# Christmas_Star.net
KiCad netlist of a schematic drawn in EAGLE
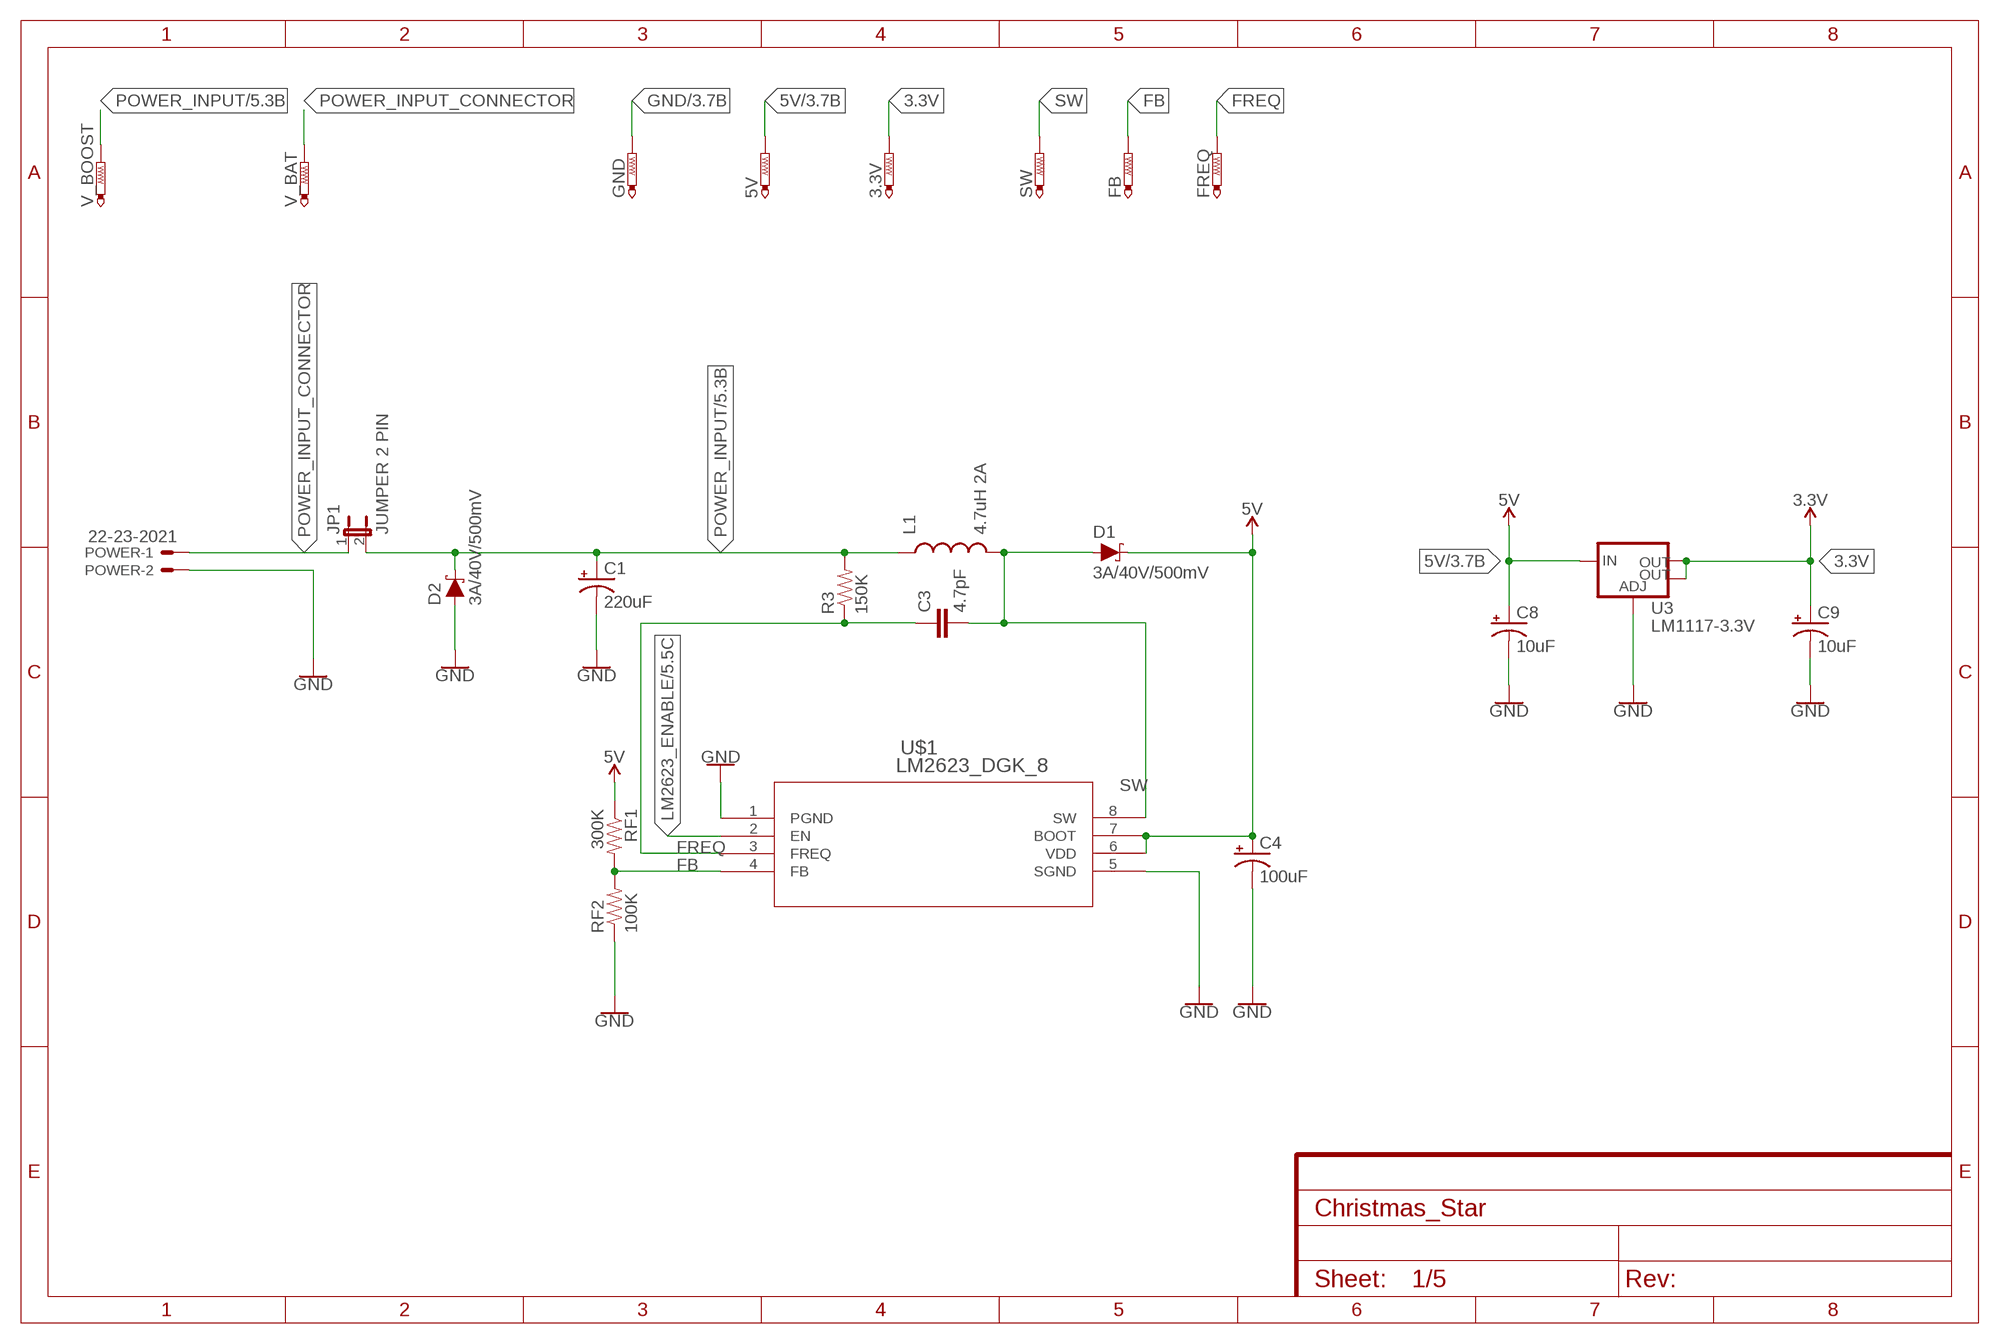
[diagram p0: schematic, sheet 1]
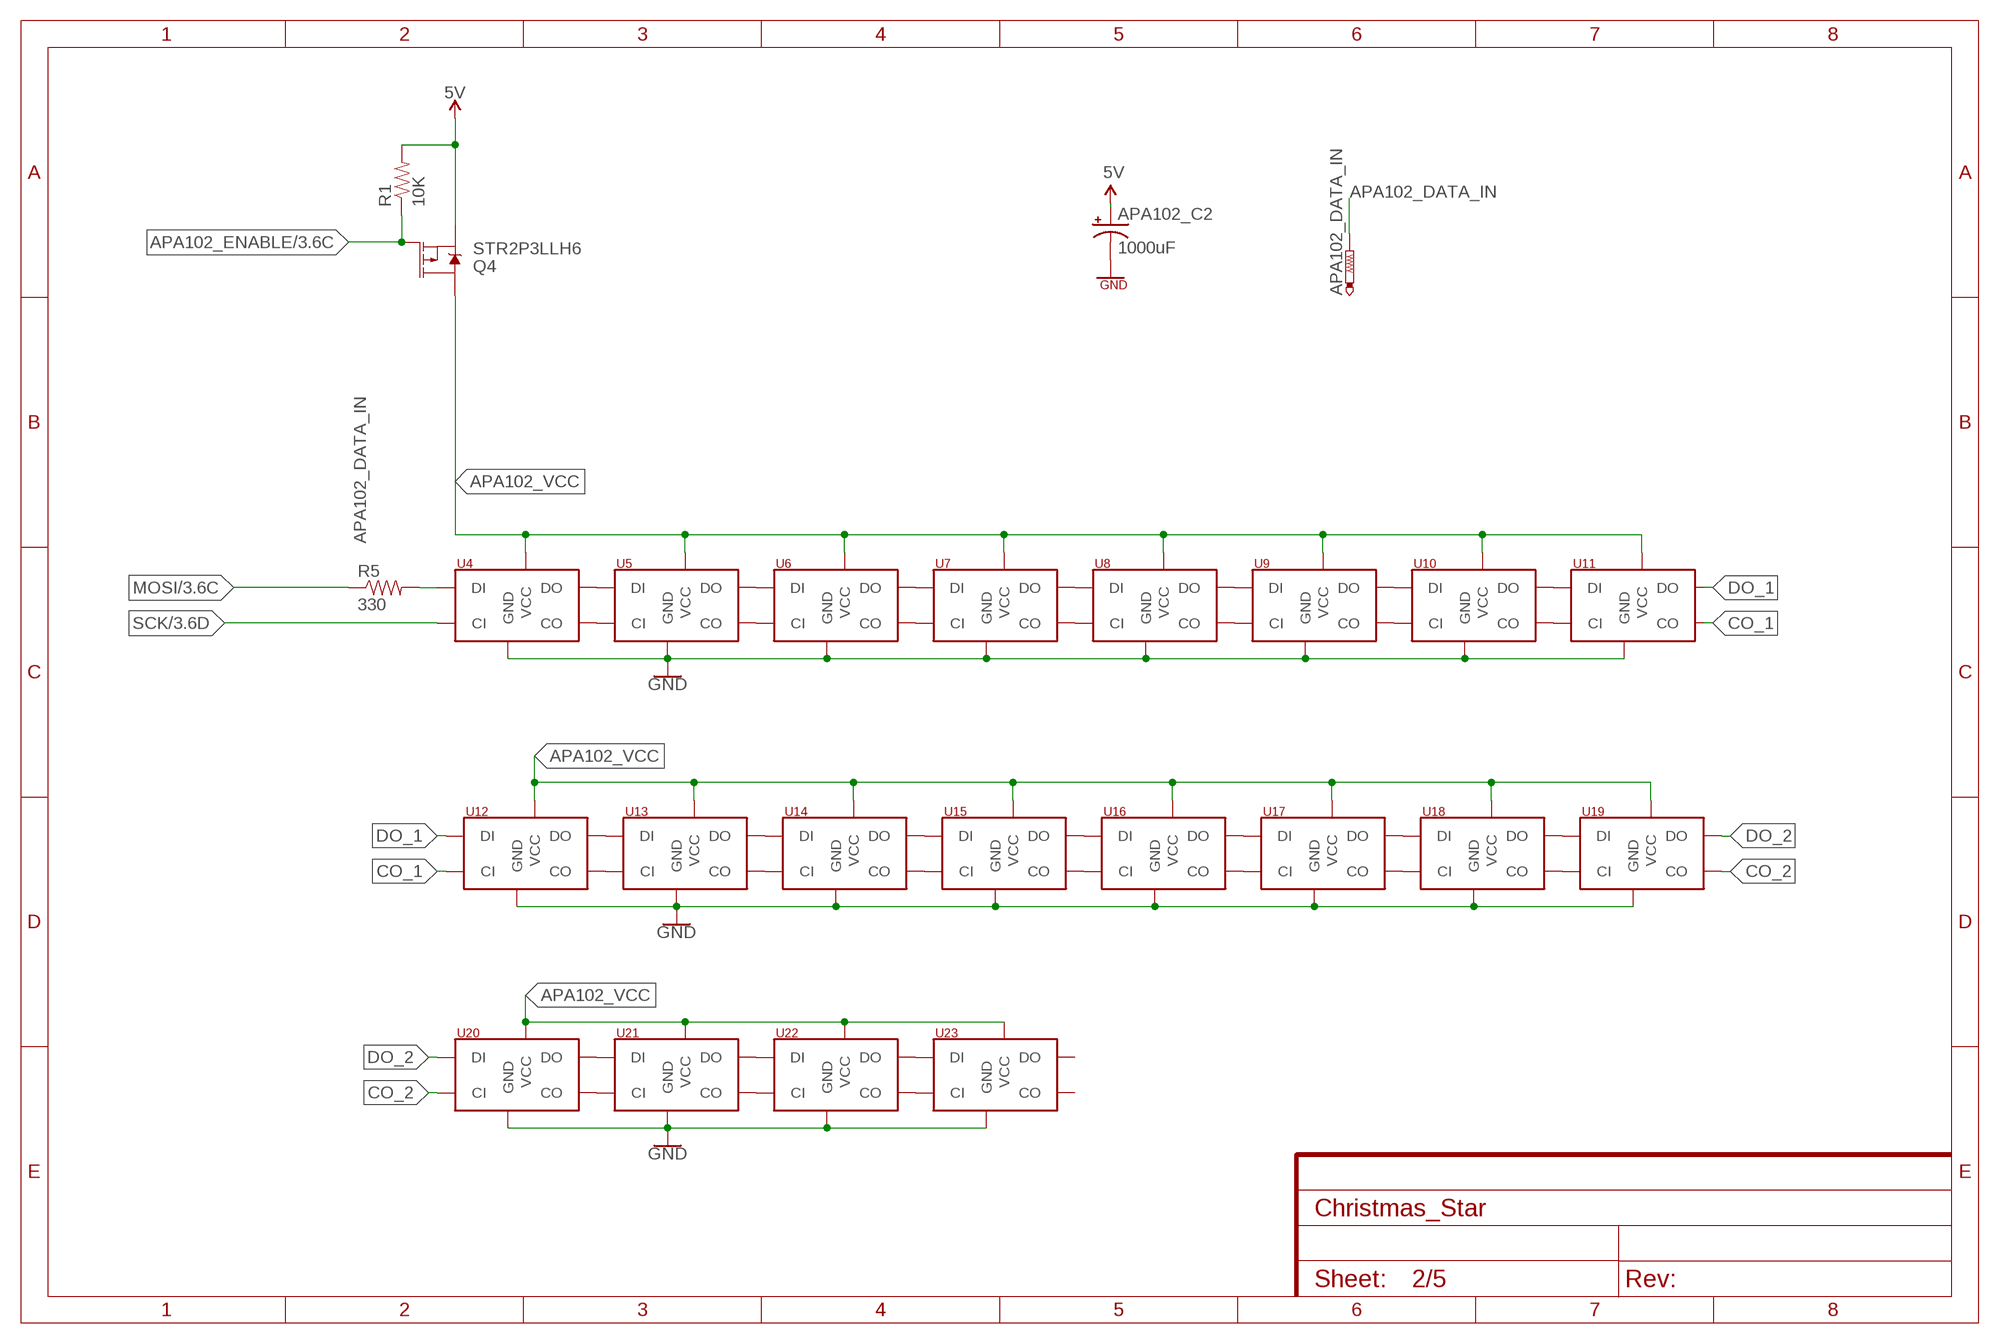
[diagram p1: schematic, sheet 2]
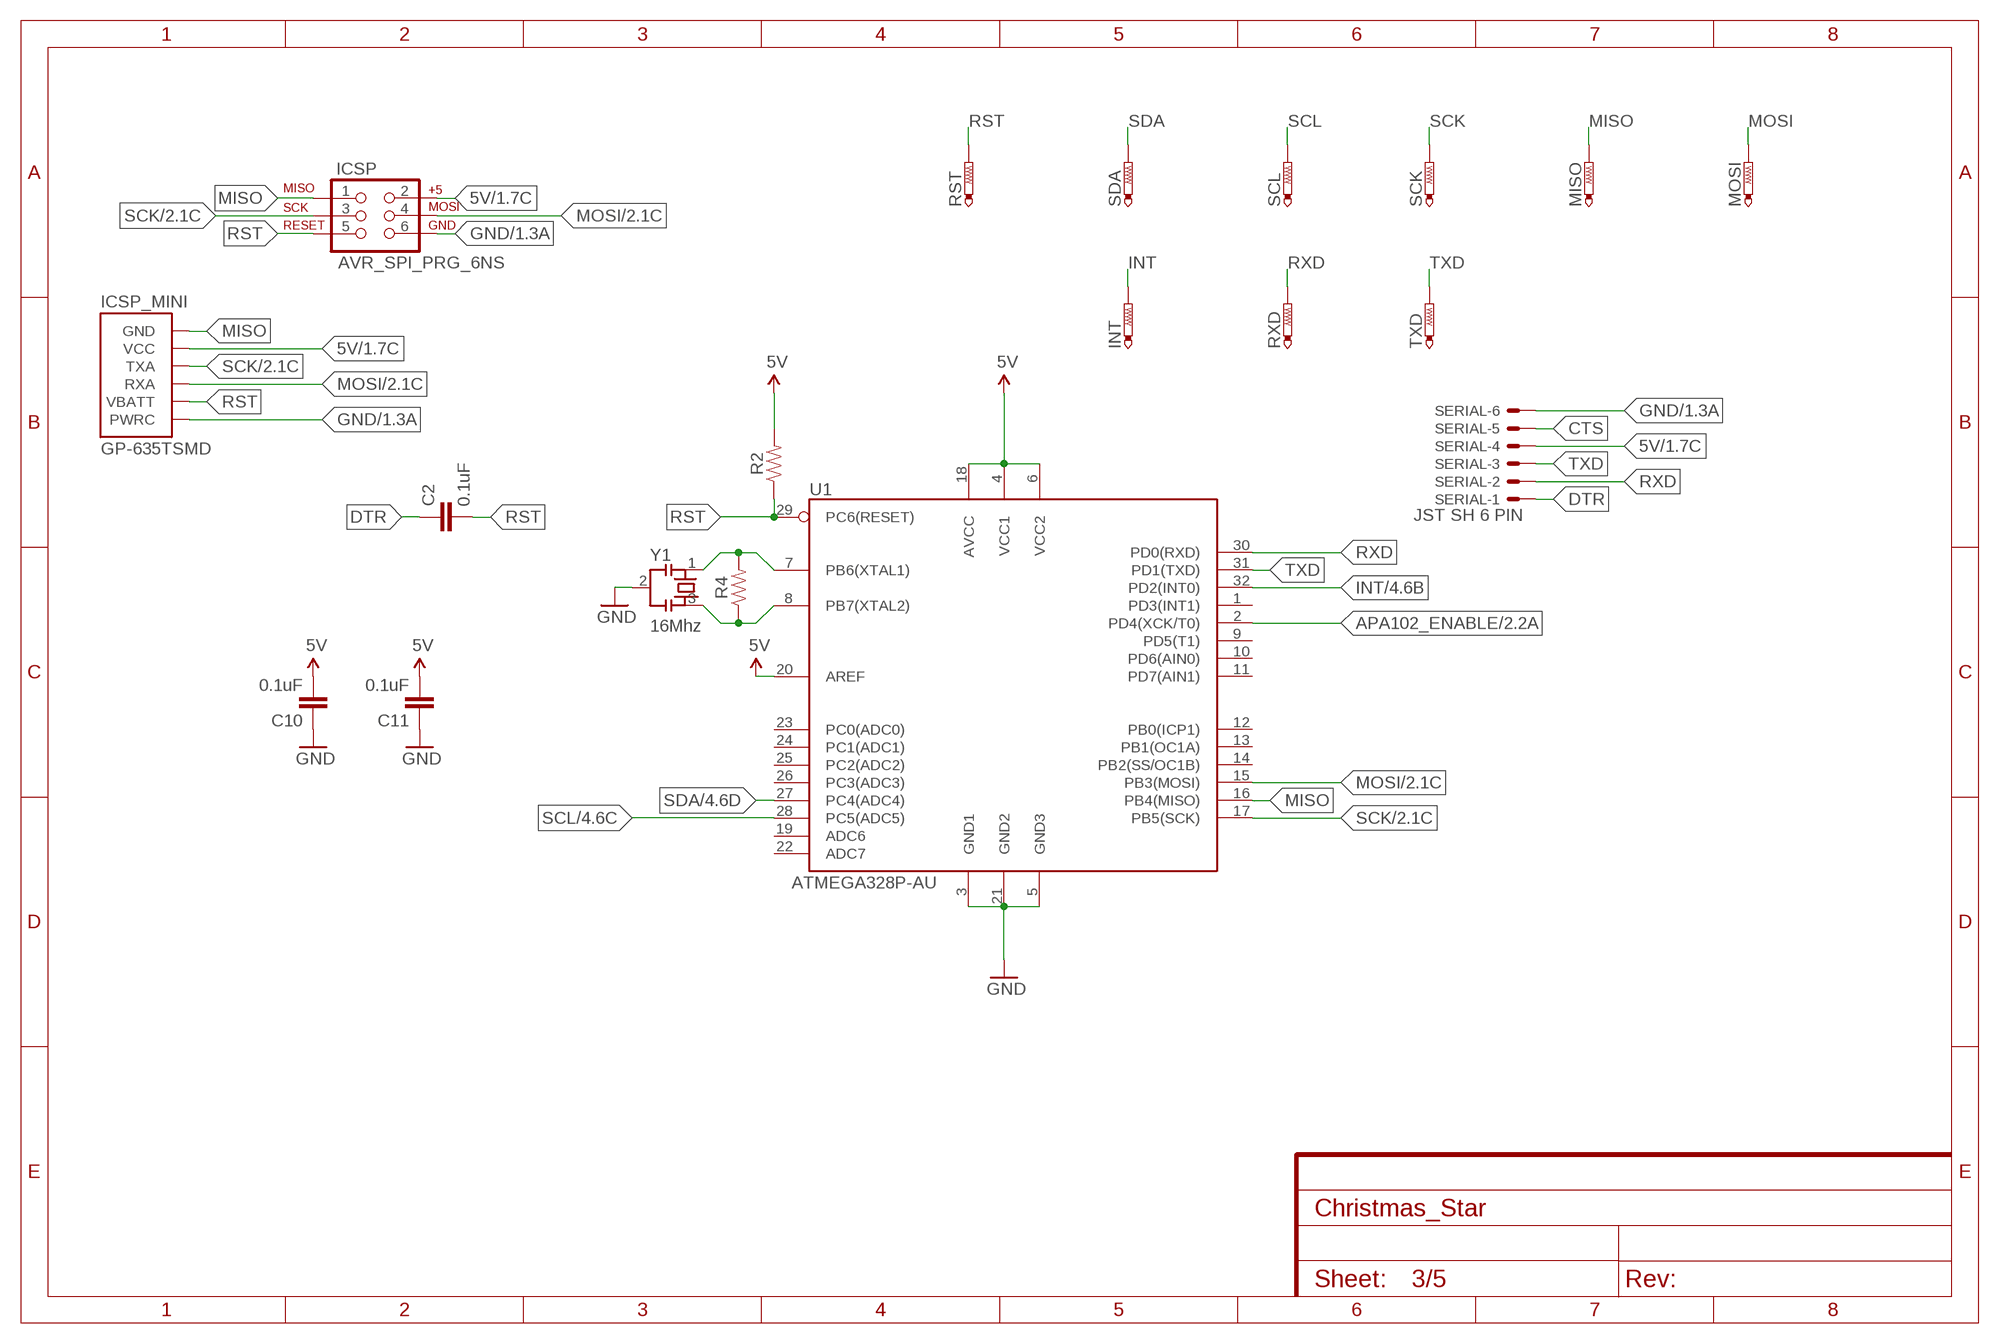
[diagram p2: schematic, sheet 3]
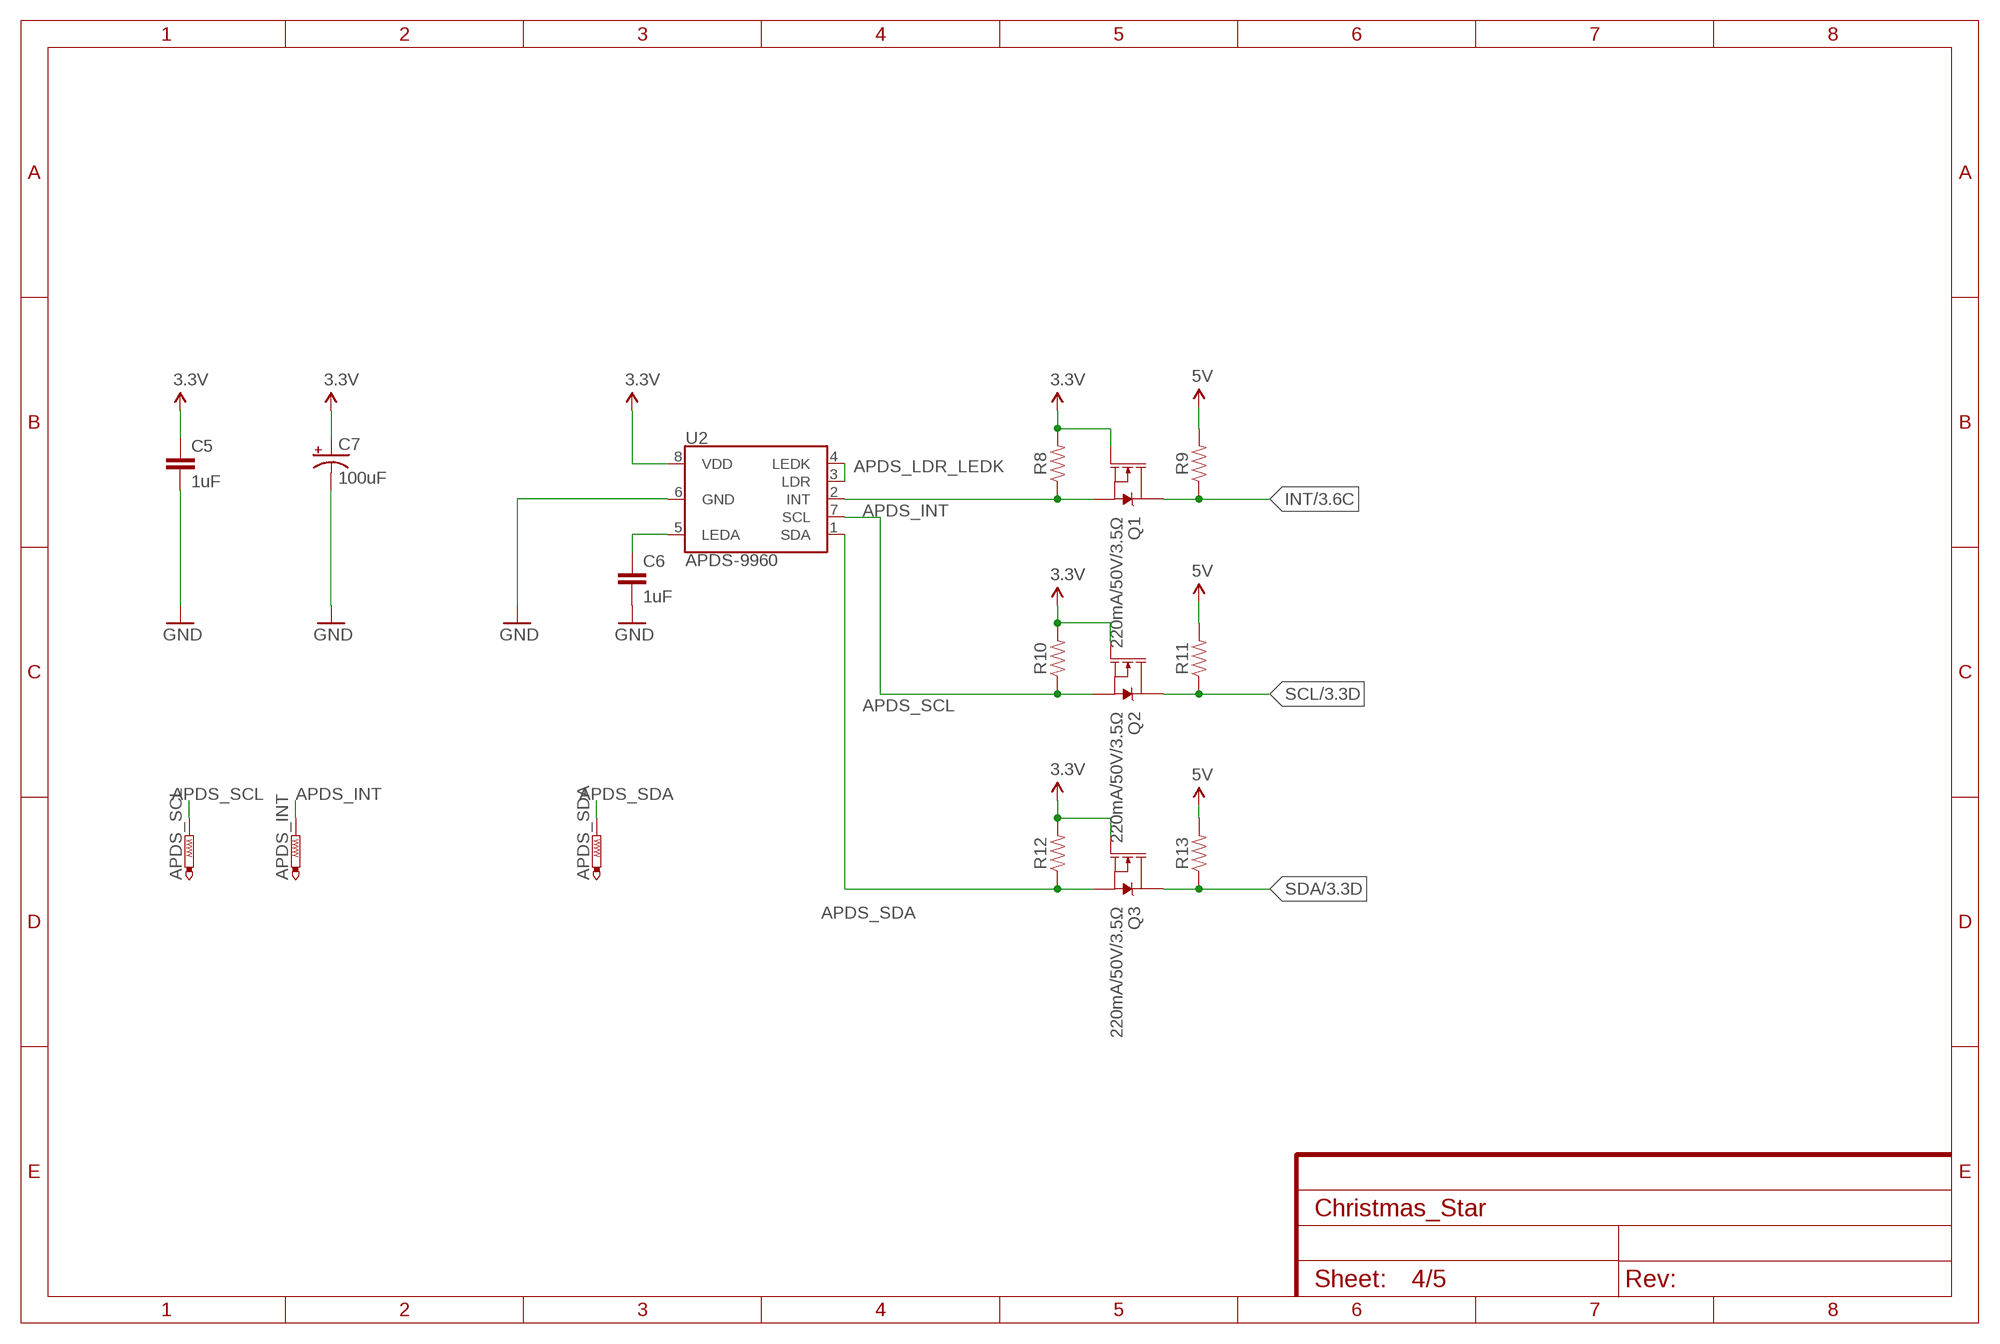
[diagram p3: schematic, sheet 4]
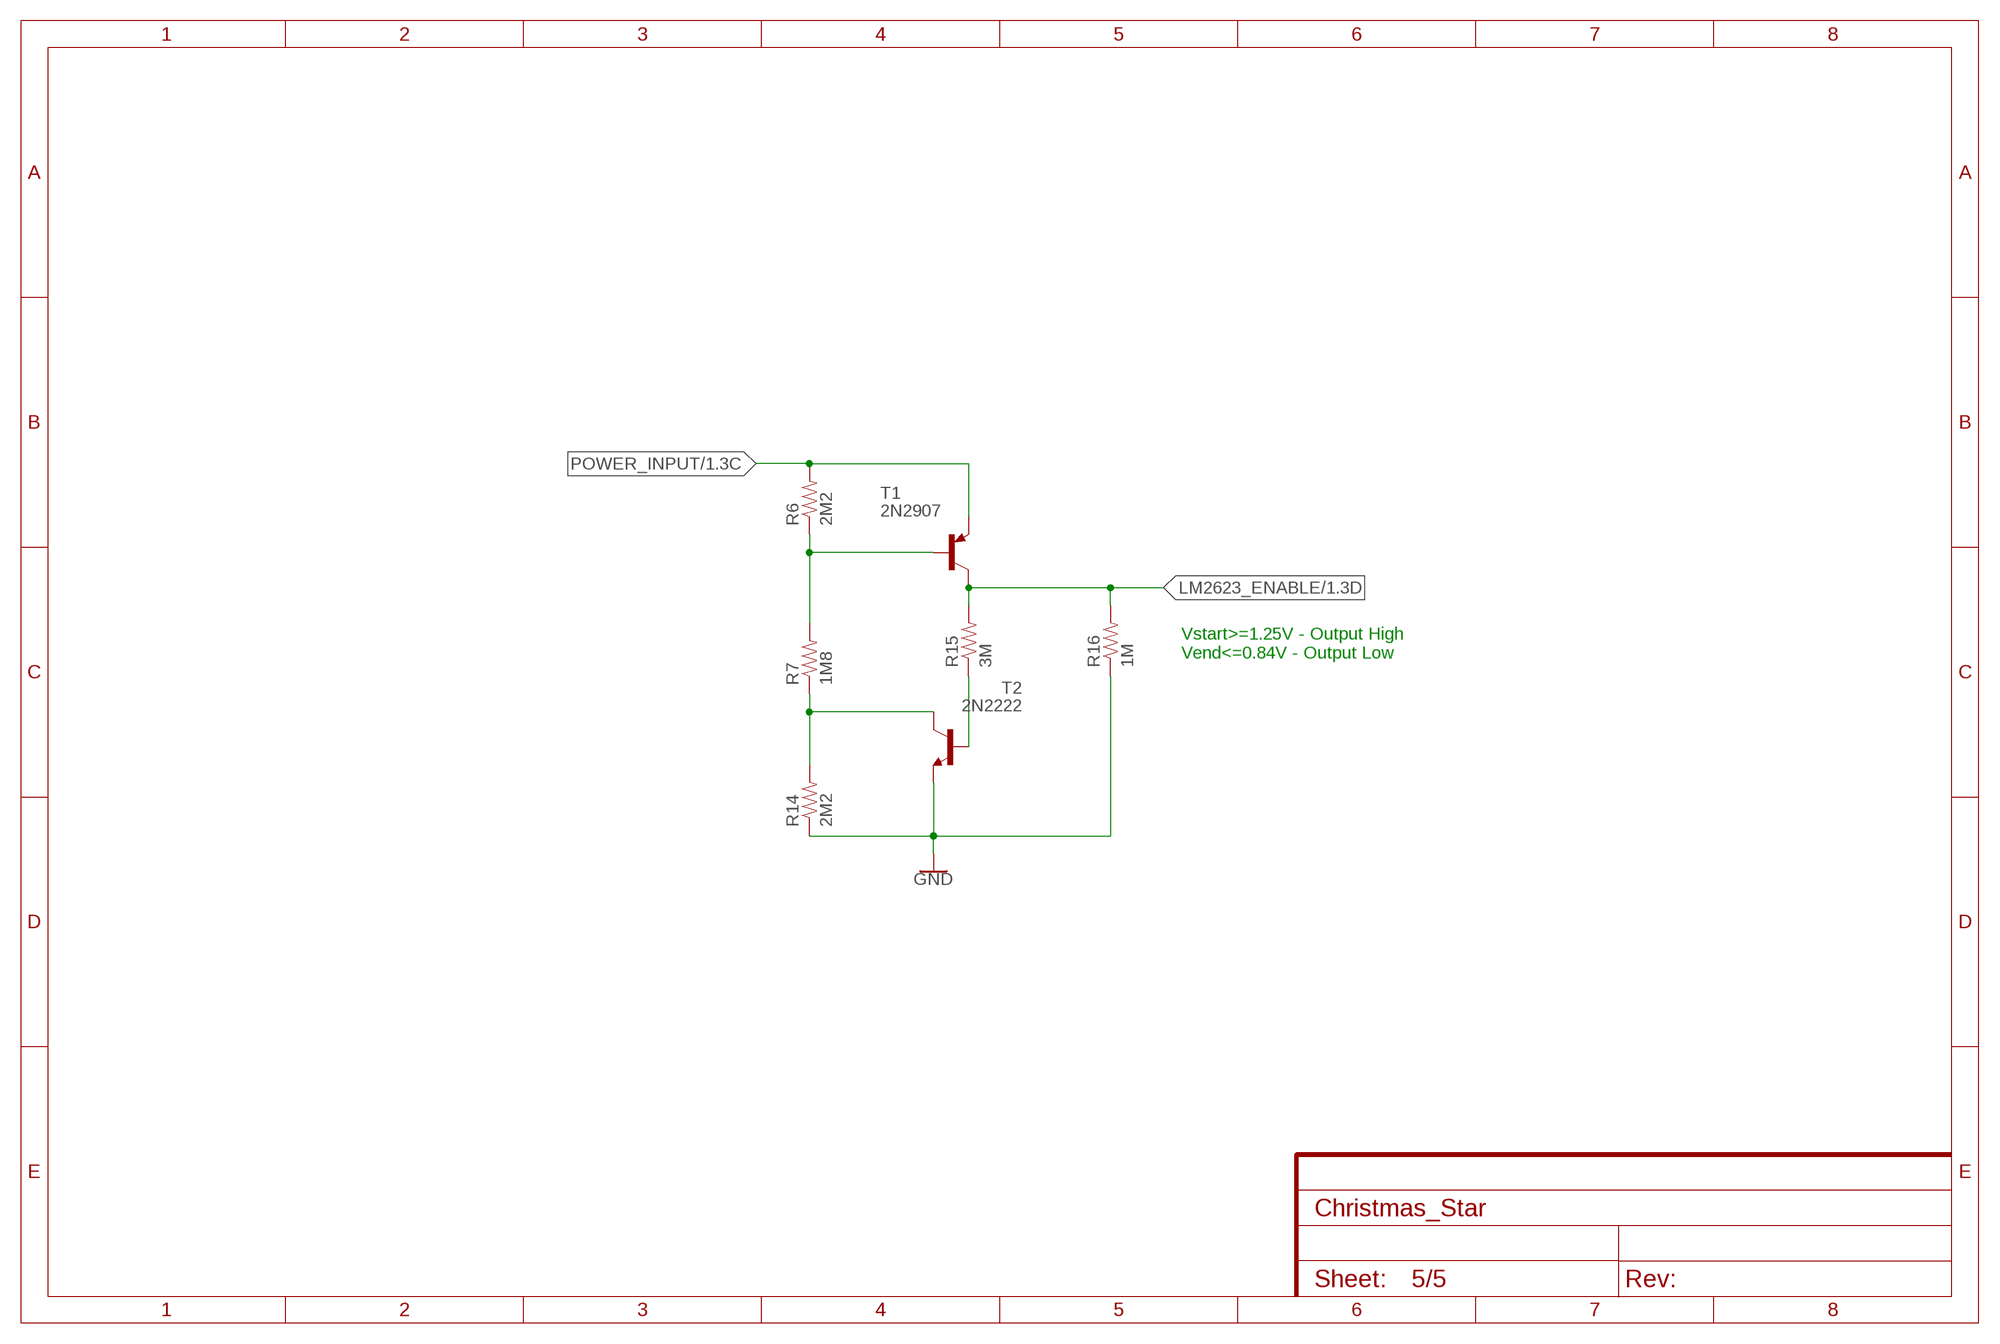
[diagram p4: schematic, sheet 5]

(export (version "E")
  (design (tool "Eeschema 10.0.6"))
  (components
    (comp (ref "3.3V")
      (value "PTR1PAD1-13")
      (footprint "eagle-import:P1-13")
      (libsource (lib "eagle-import") (part "PTR1PAD1-13"))
    )
    (comp (ref "5V")
      (value "PTR1PAD1-13")
      (footprint "eagle-import:P1-13")
      (libsource (lib "eagle-import") (part "PTR1PAD1-13"))
    )
    (comp (ref "C1")
      (value "220uF")
      (footprint "eagle-import:EIA3216-KIT")
      (libsource (lib "eagle-import") (part "CAP_POL1206-KIT"))
    )
    (comp (ref "C3")
      (value "4.7pF")
      (footprint "eagle-import:0603-CAP")
      (libsource (lib "eagle-import") (part "CAP0603-CAP"))
    )
    (comp (ref "C4")
      (value "100uF")
      (footprint "eagle-import:B_3528-21R")
      (libsource (lib "eagle-import") (part "CPOL-USB/3528-21R"))
    )
    (comp (ref "C8")
      (value "10uF")
      (footprint "eagle-import:EIA3216")
      (libsource (lib "eagle-import") (part "CAP_POL1206"))
    )
    (comp (ref "C9")
      (value "10uF")
      (footprint "eagle-import:EIA3216")
      (libsource (lib "eagle-import") (part "CAP_POL1206"))
    )
    (comp (ref "D1")
      (value "3A/40V/500mV")
      (footprint "eagle-import:SMA-DIODE")
      (libsource (lib "eagle-import") (part "DIODE-SCHOTTKY-B340A"))
    )
    (comp (ref "D2")
      (value "3A/40V/500mV")
      (footprint "eagle-import:SMA-DIODE")
      (libsource (lib "eagle-import") (part "DIODE-SCHOTTKY-B340A"))
    )
    (comp (ref "FB")
      (value "PTR1PAD1-13")
      (footprint "eagle-import:P1-13")
      (libsource (lib "eagle-import") (part "PTR1PAD1-13"))
    )
    (comp (ref "FREQ")
      (value "PTR1PAD1-13")
      (footprint "eagle-import:P1-13")
      (libsource (lib "eagle-import") (part "PTR1PAD1-13"))
    )
    (comp (ref "GND")
      (value "PTR1PAD1-13")
      (footprint "eagle-import:P1-13")
      (libsource (lib "eagle-import") (part "PTR1PAD1-13"))
    )
    (comp (ref "JP1")
      (value "JUMPER 2 PIN")
      (footprint "eagle-import:1X02_LOCK")
      (libsource (lib "eagle-import") (part "JUMPER-2PTH_LOCK"))
    )
    (comp (ref "L1")
      (value "4.7uH 2A")
      (footprint "eagle-import:CR54-KIT")
      (libsource (lib "eagle-import") (part "INDUCTORCR54-KIT"))
    )
    (comp (ref "POWER")
      (value "22-23-2021")
      (footprint "eagle-import:22-23-2021")
      (fields (field (name "MF") "MOLEX"))
      (libsource (lib "eagle-import") (part "22-23-2021"))
    )
    (comp (ref "R3")
      (value "150K")
      (footprint "eagle-import:0603-RES")
      (libsource (lib "eagle-import") (part "RESISTOR0603-RES"))
    )
    (comp (ref "RF1")
      (value "300K")
      (footprint "eagle-import:0603-RES")
      (libsource (lib "eagle-import") (part "RESISTOR0603-RES"))
    )
    (comp (ref "RF2")
      (value "100K")
      (footprint "eagle-import:0603-RES")
      (libsource (lib "eagle-import") (part "RESISTOR0603-RES"))
    )
    (comp (ref "SW")
      (value "PTR1PAD1-13")
      (footprint "eagle-import:P1-13")
      (libsource (lib "eagle-import") (part "PTR1PAD1-13"))
    )
    (comp (ref "U$1")
      (value "LM2623_DGK_8")
      (footprint "eagle-import:MUA08A")
      (fields (field (name "MANUFACTURER_PART_NUMBER") "lm2623ammnopb"))
      (libsource (lib "eagle-import") (part "LM2623_DGK_8"))
    )
    (comp (ref "U3")
      (value "LM1117-3.3V")
      (footprint "eagle-import:SOT223")
      (libsource (lib "eagle-import") (part "V_REG_LM1117SOT223"))
    )
    (comp (ref "V_BAT")
      (value "PTR1PAD1-13")
      (footprint "eagle-import:P1-13")
      (libsource (lib "eagle-import") (part "PTR1PAD1-13"))
    )
    (comp (ref "V_BOOST")
      (value "PTR1PAD1-13")
      (footprint "eagle-import:P1-13")
      (libsource (lib "eagle-import") (part "PTR1PAD1-13"))
    )
    (comp (ref "C2")
      (value "0.1uF")
      (footprint "eagle-import:0603-CAP")
      (libsource (lib "eagle-import") (part "SparkFun-Passives_CAP0603-CAP"))
    )
    (comp (ref "C10")
      (value "0.1uF")
      (footprint "eagle-import:0603-CAP")
      (libsource (lib "eagle-import") (part "SparkFun-Passives_CAP0603-CAP"))
    )
    (comp (ref "C11")
      (value "0.1uF")
      (footprint "eagle-import:0603-CAP")
      (libsource (lib "eagle-import") (part "SparkFun-Passives_CAP0603-CAP"))
    )
    (comp (ref "ICSP")
      (value "AVR_SPI_PRG_6NS")
      (footprint "eagle-import:2X3-NS")
      (libsource (lib "eagle-import") (part "AVR_SPI_PRG_6NS"))
    )
    (comp (ref "ICSP_MINI")
      (value "GP-635TSMD")
      (footprint "eagle-import:GP-635T")
      (libsource (lib "eagle-import") (part "GP-635TSMD"))
    )
    (comp (ref "INT")
      (value "PTR1PAD1-13")
      (footprint "eagle-import:P1-13")
      (libsource (lib "eagle-import") (part "PTR1PAD1-13"))
    )
    (comp (ref "MISO")
      (value "PTR1PAD1-13")
      (footprint "eagle-import:P1-13")
      (libsource (lib "eagle-import") (part "PTR1PAD1-13"))
    )
    (comp (ref "MOSI")
      (value "PTR1PAD1-13")
      (footprint "eagle-import:P1-13")
      (libsource (lib "eagle-import") (part "PTR1PAD1-13"))
    )
    (comp (ref "R2")
      (value "RESISTOR0603")
      (footprint "eagle-import:0603")
      (libsource (lib "eagle-import") (part "RESISTOR0603"))
    )
    (comp (ref "R4")
      (value "RESISTOR0603")
      (footprint "eagle-import:0603")
      (libsource (lib "eagle-import") (part "RESISTOR0603"))
    )
    (comp (ref "RST")
      (value "PTR1PAD1-13")
      (footprint "eagle-import:P1-13")
      (libsource (lib "eagle-import") (part "PTR1PAD1-13"))
    )
    (comp (ref "RXD")
      (value "PTR1PAD1-13")
      (footprint "eagle-import:P1-13")
      (libsource (lib "eagle-import") (part "PTR1PAD1-13"))
    )
    (comp (ref "SCK")
      (value "PTR1PAD1-13")
      (footprint "eagle-import:P1-13")
      (libsource (lib "eagle-import") (part "PTR1PAD1-13"))
    )
    (comp (ref "SCL")
      (value "PTR1PAD1-13")
      (footprint "eagle-import:P1-13")
      (libsource (lib "eagle-import") (part "PTR1PAD1-13"))
    )
    (comp (ref "SDA")
      (value "PTR1PAD1-13")
      (footprint "eagle-import:P1-13")
      (libsource (lib "eagle-import") (part "PTR1PAD1-13"))
    )
    (comp (ref "SERIAL")
      (value "JST SH 6 PIN")
      (footprint "eagle-import:22-23-2061")
      (fields (field (name "MF") "MOLEX") (field (name "MPN") "22-23-2061"))
      (libsource (lib "eagle-import") (part "22-23-2061"))
    )
    (comp (ref "TXD")
      (value "PTR1PAD1-13")
      (footprint "eagle-import:P1-13")
      (libsource (lib "eagle-import") (part "PTR1PAD1-13"))
    )
    (comp (ref "U1")
      (value "ATMEGA328P-AU")
      (footprint "eagle-import:TQFP32")
      (libsource (lib "eagle-import") (part "ATMEGA328P-AU"))
    )
    (comp (ref "Y1")
      (value "16Mhz")
      (footprint "eagle-import:CSTCE")
      (libsource (lib "eagle-import") (part "CSTCE"))
    )
    (comp (ref "APDS_INT")
      (value "PTR1PAD1-13")
      (footprint "eagle-import:P1-13")
      (libsource (lib "eagle-import") (part "PTR1PAD1-13"))
    )
    (comp (ref "APDS_SCL")
      (value "PTR1PAD1-13")
      (footprint "eagle-import:P1-13")
      (libsource (lib "eagle-import") (part "PTR1PAD1-13"))
    )
    (comp (ref "APDS_SDA")
      (value "PTR1PAD1-13")
      (footprint "eagle-import:P1-13")
      (libsource (lib "eagle-import") (part "PTR1PAD1-13"))
    )
    (comp (ref "C5")
      (value "1uF")
      (footprint "eagle-import:0603-CAP")
      (libsource (lib "eagle-import") (part "SparkFun-Passives_CAP0603-CAP"))
    )
    (comp (ref "C6")
      (value "1uF")
      (footprint "eagle-import:0603-CAP")
      (libsource (lib "eagle-import") (part "SparkFun-Passives_CAP0603-CAP"))
    )
    (comp (ref "C7")
      (value "100uF")
      (footprint "eagle-import:EIA3216-KIT")
      (libsource (lib "eagle-import") (part "CAP_POL1206-KIT"))
    )
    (comp (ref "Q1")
      (value "220mA/50V/3.5Ω")
      (footprint "eagle-import:SOT23-3")
      (libsource (lib "eagle-import") (part "MOSFET-NCH-BSS138"))
    )
    (comp (ref "Q2")
      (value "220mA/50V/3.5Ω")
      (footprint "eagle-import:SOT23-3")
      (libsource (lib "eagle-import") (part "MOSFET-NCH-BSS138"))
    )
    (comp (ref "Q3")
      (value "220mA/50V/3.5Ω")
      (footprint "eagle-import:SOT23-3")
      (libsource (lib "eagle-import") (part "MOSFET-NCH-BSS138"))
    )
    (comp (ref "R8")
      (value "RESISTOR0603")
      (footprint "eagle-import:0603")
      (libsource (lib "eagle-import") (part "RESISTOR0603"))
    )
    (comp (ref "R9")
      (value "RESISTOR0603")
      (footprint "eagle-import:0603")
      (libsource (lib "eagle-import") (part "RESISTOR0603"))
    )
    (comp (ref "R10")
      (value "RESISTOR0603")
      (footprint "eagle-import:0603")
      (libsource (lib "eagle-import") (part "RESISTOR0603"))
    )
    (comp (ref "R11")
      (value "RESISTOR0603")
      (footprint "eagle-import:0603")
      (libsource (lib "eagle-import") (part "RESISTOR0603"))
    )
    (comp (ref "R12")
      (value "RESISTOR0603")
      (footprint "eagle-import:0603")
      (libsource (lib "eagle-import") (part "RESISTOR0603"))
    )
    (comp (ref "R13")
      (value "RESISTOR0603")
      (footprint "eagle-import:0603")
      (libsource (lib "eagle-import") (part "RESISTOR0603"))
    )
    (comp (ref "U2")
      (value "APDS-9960")
      (footprint "eagle-import:APDS-9960")
      (libsource (lib "eagle-import") (part "APDS-9960"))
    )
    (comp (ref "R6")
      (value "2M2")
      (footprint "eagle-import:0603-RES")
      (libsource (lib "eagle-import") (part "RESISTOR0603-RES"))
    )
    (comp (ref "R7")
      (value "1M8")
      (footprint "eagle-import:0603-RES")
      (libsource (lib "eagle-import") (part "RESISTOR0603-RES"))
    )
    (comp (ref "R14")
      (value "2M2")
      (footprint "eagle-import:0603-RES")
      (libsource (lib "eagle-import") (part "RESISTOR0603-RES"))
    )
    (comp (ref "R15")
      (value "3M")
      (footprint "eagle-import:0603-RES")
      (libsource (lib "eagle-import") (part "RESISTOR0603-RES"))
    )
    (comp (ref "R16")
      (value "1M")
      (footprint "eagle-import:0603-RES")
      (libsource (lib "eagle-import") (part "RESISTOR0603-RES"))
    )
    (comp (ref "T1")
      (value "2N2907")
      (footprint "eagle-import:SOT23-BEC")
      (libsource (lib "eagle-import") (part "-PNP-SOT23-BECMMBT2907ALT1"))
    )
    (comp (ref "T2")
      (value "2N2222")
      (footprint "eagle-import:SOT23-BEC")
      (libsource (lib "eagle-import") (part "-NPN-SOT23-BECMMBT2222ALT1"))
    )
    (comp (ref "APA102_C2")
      (value "1000uF")
      (footprint "eagle-import:D_7343-31W")
      (libsource (lib "eagle-import") (part "resistor_CPOL-USD/7343-31W"))
    )
    (comp (ref "APA102_DATA_IN")
      (value "PTR1PAD1-13")
      (footprint "eagle-import:P1-13")
      (libsource (lib "eagle-import") (part "PTR1PAD1-13"))
    )
    (comp (ref "Q4")
      (value "STR2P3LLH6")
      (footprint "eagle-import:SOT23-3")
      (libsource (lib "eagle-import") (part "MOSFET_PCH-IRLML2244"))
    )
    (comp (ref "R1")
      (value "10K")
      (footprint "eagle-import:1206")
      (libsource (lib "eagle-import") (part "RESISTOR1206"))
    )
    (comp (ref "R5")
      (value "330")
      (footprint "eagle-import:0603-RES")
      (libsource (lib "eagle-import") (part "RESISTOR0603-RES"))
    )
    (comp (ref "U4")
      (value "APA1022020")
      (footprint "eagle-import:APA102_2020")
      (libsource (lib "eagle-import") (part "APA1022020"))
    )
    (comp (ref "U5")
      (value "APA1022020")
      (footprint "eagle-import:APA102_2020")
      (libsource (lib "eagle-import") (part "APA1022020"))
    )
    (comp (ref "U6")
      (value "APA1022020")
      (footprint "eagle-import:APA102_2020")
      (libsource (lib "eagle-import") (part "APA1022020"))
    )
    (comp (ref "U7")
      (value "APA1022020")
      (footprint "eagle-import:APA102_2020")
      (libsource (lib "eagle-import") (part "APA1022020"))
    )
    (comp (ref "U8")
      (value "APA1022020")
      (footprint "eagle-import:APA102_2020")
      (libsource (lib "eagle-import") (part "APA1022020"))
    )
    (comp (ref "U9")
      (value "APA1022020")
      (footprint "eagle-import:APA102_2020")
      (libsource (lib "eagle-import") (part "APA1022020"))
    )
    (comp (ref "U10")
      (value "APA1022020")
      (footprint "eagle-import:APA102_2020")
      (libsource (lib "eagle-import") (part "APA1022020"))
    )
    (comp (ref "U11")
      (value "APA1022020")
      (footprint "eagle-import:APA102_2020")
      (libsource (lib "eagle-import") (part "APA1022020"))
    )
    (comp (ref "U12")
      (value "APA1022020")
      (footprint "eagle-import:APA102_2020")
      (libsource (lib "eagle-import") (part "APA1022020"))
    )
    (comp (ref "U13")
      (value "APA1022020")
      (footprint "eagle-import:APA102_2020")
      (libsource (lib "eagle-import") (part "APA1022020"))
    )
    (comp (ref "U14")
      (value "APA1022020")
      (footprint "eagle-import:APA102_2020")
      (libsource (lib "eagle-import") (part "APA1022020"))
    )
    (comp (ref "U15")
      (value "APA1022020")
      (footprint "eagle-import:APA102_2020")
      (libsource (lib "eagle-import") (part "APA1022020"))
    )
    (comp (ref "U16")
      (value "APA1022020")
      (footprint "eagle-import:APA102_2020")
      (libsource (lib "eagle-import") (part "APA1022020"))
    )
    (comp (ref "U17")
      (value "APA1022020")
      (footprint "eagle-import:APA102_2020")
      (libsource (lib "eagle-import") (part "APA1022020"))
    )
    (comp (ref "U18")
      (value "APA1022020")
      (footprint "eagle-import:APA102_2020")
      (libsource (lib "eagle-import") (part "APA1022020"))
    )
    (comp (ref "U19")
      (value "APA1022020")
      (footprint "eagle-import:APA102_2020")
      (libsource (lib "eagle-import") (part "APA1022020"))
    )
    (comp (ref "U20")
      (value "APA1022020")
      (footprint "eagle-import:APA102_2020")
      (libsource (lib "eagle-import") (part "APA1022020"))
    )
    (comp (ref "U21")
      (value "APA1022020")
      (footprint "eagle-import:APA102_2020")
      (libsource (lib "eagle-import") (part "APA1022020"))
    )
    (comp (ref "U22")
      (value "APA1022020")
      (footprint "eagle-import:APA102_2020")
      (libsource (lib "eagle-import") (part "APA1022020"))
    )
    (comp (ref "U23")
      (value "APA1022020")
      (footprint "eagle-import:APA102_2020")
      (libsource (lib "eagle-import") (part "APA1022020"))
    )
  )
  (nets
    (net (code "1") (name "3.3V") (class "Default")
      (node (ref "3.3V") (pin "TP") (pinfunction "TP_TP") (pintype "input"))
      (node (ref "C5") (pin "1") (pinfunction "1_1") (pintype "passive"))
      (node (ref "C7") (pin "A") (pinfunction "+_A") (pintype "passive"))
      (node (ref "C9") (pin "A") (pinfunction "+_A") (pintype "passive"))
      (node (ref "Q1") (pin "1") (pinfunction "G_1") (pintype "bidirectional"))
      (node (ref "Q2") (pin "1") (pinfunction "G_1") (pintype "bidirectional"))
      (node (ref "Q3") (pin "1") (pinfunction "G_1") (pintype "bidirectional"))
      (node (ref "R10") (pin "2") (pinfunction "2_2") (pintype "passive"))
      (node (ref "R12") (pin "2") (pinfunction "2_2") (pintype "passive"))
      (node (ref "R8") (pin "2") (pinfunction "2_2") (pintype "passive"))
      (node (ref "U2") (pin "8") (pinfunction "VDD_8") (pintype "bidirectional"))
      (node (ref "U3") (pin "2") (pinfunction "OUT_2") (pintype "output"))
      (node (ref "U3") (pin "4") (pinfunction "OUT_4") (pintype "output"))
    )
    (net (code "2") (name "5V") (class "Default")
      (node (ref "5V") (pin "TP") (pinfunction "TP_TP") (pintype "input"))
      (node (ref "APA102_C2") (pin "+") (pinfunction "+_+") (pintype "passive"))
      (node (ref "C10") (pin "2") (pinfunction "2_2") (pintype "passive"))
      (node (ref "C11") (pin "2") (pinfunction "2_2") (pintype "passive"))
      (node (ref "C4") (pin "+") (pinfunction "+_+") (pintype "passive"))
      (node (ref "C8") (pin "A") (pinfunction "+_A") (pintype "passive"))
      (node (ref "D1") (pin "C") (pinfunction "C_C") (pintype "passive"))
      (node (ref "ICSP") (pin "2") (pinfunction "2_2") (pintype "passive"))
      (node (ref "ICSP_MINI") (pin "2") (pinfunction "VCC_2") (pintype "power_in"))
      (node (ref "Q4") (pin "2") (pinfunction "S_2") (pintype "bidirectional"))
      (node (ref "R1") (pin "2") (pinfunction "2_2") (pintype "passive"))
      (node (ref "R11") (pin "2") (pinfunction "2_2") (pintype "passive"))
      (node (ref "R13") (pin "2") (pinfunction "2_2") (pintype "passive"))
      (node (ref "R2") (pin "2") (pinfunction "2_2") (pintype "passive"))
      (node (ref "R9") (pin "2") (pinfunction "2_2") (pintype "passive"))
      (node (ref "RF1") (pin "1") (pinfunction "1_1") (pintype "passive"))
      (node (ref "SERIAL") (pin "4") (pinfunction "S_4") (pintype "passive"))
      (node (ref "U$1") (pin "6") (pinfunction "VDD_6") (pintype "power_in"))
      (node (ref "U$1") (pin "7") (pinfunction "BOOT_7") (pintype "passive"))
      (node (ref "U1") (pin "18") (pinfunction "AVCC_18") (pintype "bidirectional"))
      (node (ref "U1") (pin "20") (pinfunction "AREF_20") (pintype "bidirectional"))
      (node (ref "U1") (pin "4") (pinfunction "VCC1_4") (pintype "bidirectional"))
      (node (ref "U1") (pin "6") (pinfunction "VCC2_6") (pintype "bidirectional"))
      (node (ref "U3") (pin "3") (pinfunction "IN_3") (pintype "input"))
    )
    (net (code "3") (name "APA102_DATA_IN") (class "Default")
      (node (ref "APA102_DATA_IN") (pin "TP") (pinfunction "TP_TP") (pintype "input"))
      (node (ref "R5") (pin "2") (pinfunction "2_2") (pintype "passive"))
      (node (ref "U4") (pin "D_IN") (pinfunction "DI_D_IN") (pintype "bidirectional"))
    )
    (net (code "4") (name "APA102_ENABLE") (class "Default")
      (node (ref "Q4") (pin "1") (pinfunction "G_1") (pintype "bidirectional"))
      (node (ref "R1") (pin "1") (pinfunction "1_1") (pintype "passive"))
      (node (ref "U1") (pin "2") (pinfunction "PD4(XCK/T0)_2") (pintype "bidirectional"))
    )
    (net (code "5") (name "APA102_VCC") (class "Default")
      (node (ref "Q4") (pin "3") (pinfunction "D_3") (pintype "bidirectional"))
      (node (ref "U10") (pin "V_CC") (pinfunction "VCC_V_CC") (pintype "bidirectional"))
      (node (ref "U11") (pin "V_CC") (pinfunction "VCC_V_CC") (pintype "bidirectional"))
      (node (ref "U12") (pin "V_CC") (pinfunction "VCC_V_CC") (pintype "bidirectional"))
      (node (ref "U13") (pin "V_CC") (pinfunction "VCC_V_CC") (pintype "bidirectional"))
      (node (ref "U14") (pin "V_CC") (pinfunction "VCC_V_CC") (pintype "bidirectional"))
      (node (ref "U15") (pin "V_CC") (pinfunction "VCC_V_CC") (pintype "bidirectional"))
      (node (ref "U16") (pin "V_CC") (pinfunction "VCC_V_CC") (pintype "bidirectional"))
      (node (ref "U17") (pin "V_CC") (pinfunction "VCC_V_CC") (pintype "bidirectional"))
      (node (ref "U18") (pin "V_CC") (pinfunction "VCC_V_CC") (pintype "bidirectional"))
      (node (ref "U19") (pin "V_CC") (pinfunction "VCC_V_CC") (pintype "bidirectional"))
      (node (ref "U20") (pin "V_CC") (pinfunction "VCC_V_CC") (pintype "bidirectional"))
      (node (ref "U21") (pin "V_CC") (pinfunction "VCC_V_CC") (pintype "bidirectional"))
      (node (ref "U22") (pin "V_CC") (pinfunction "VCC_V_CC") (pintype "bidirectional"))
      (node (ref "U23") (pin "V_CC") (pinfunction "VCC_V_CC") (pintype "bidirectional"))
      (node (ref "U4") (pin "V_CC") (pinfunction "VCC_V_CC") (pintype "bidirectional"))
      (node (ref "U5") (pin "V_CC") (pinfunction "VCC_V_CC") (pintype "bidirectional"))
      (node (ref "U6") (pin "V_CC") (pinfunction "VCC_V_CC") (pintype "bidirectional"))
      (node (ref "U7") (pin "V_CC") (pinfunction "VCC_V_CC") (pintype "bidirectional"))
      (node (ref "U8") (pin "V_CC") (pinfunction "VCC_V_CC") (pintype "bidirectional"))
      (node (ref "U9") (pin "V_CC") (pinfunction "VCC_V_CC") (pintype "bidirectional"))
    )
    (net (code "6") (name "APDS_INT") (class "Default")
      (node (ref "APDS_INT") (pin "TP") (pinfunction "TP_TP") (pintype "input"))
      (node (ref "Q1") (pin "2") (pinfunction "S_2") (pintype "bidirectional"))
      (node (ref "R8") (pin "1") (pinfunction "1_1") (pintype "passive"))
      (node (ref "U2") (pin "2") (pinfunction "INT_2") (pintype "bidirectional"))
    )
    (net (code "7") (name "APDS_LDR_LEDK") (class "Default")
      (node (ref "U2") (pin "3") (pinfunction "LDR_3") (pintype "bidirectional"))
      (node (ref "U2") (pin "4") (pinfunction "LEDK_4") (pintype "bidirectional"))
    )
    (net (code "8") (name "APDS_SCL") (class "Default")
      (node (ref "APDS_SCL") (pin "TP") (pinfunction "TP_TP") (pintype "input"))
      (node (ref "Q2") (pin "2") (pinfunction "S_2") (pintype "bidirectional"))
      (node (ref "R10") (pin "1") (pinfunction "1_1") (pintype "passive"))
      (node (ref "U2") (pin "7") (pinfunction "SCL_7") (pintype "bidirectional"))
    )
    (net (code "9") (name "APDS_SDA") (class "Default")
      (node (ref "APDS_SDA") (pin "TP") (pinfunction "TP_TP") (pintype "input"))
      (node (ref "Q3") (pin "2") (pinfunction "S_2") (pintype "bidirectional"))
      (node (ref "R12") (pin "1") (pinfunction "1_1") (pintype "passive"))
      (node (ref "U2") (pin "1") (pinfunction "SDA_1") (pintype "bidirectional"))
    )
    (net (code "10") (name "CO_1") (class "Default")
      (node (ref "U11") (pin "CL_OUT") (pinfunction "CO_CL_OUT") (pintype "bidirectional"))
      (node (ref "U12") (pin "C_IN") (pinfunction "CI_C_IN") (pintype "bidirectional"))
    )
    (net (code "11") (name "CO_2") (class "Default")
      (node (ref "U19") (pin "CL_OUT") (pinfunction "CO_CL_OUT") (pintype "bidirectional"))
      (node (ref "U20") (pin "C_IN") (pinfunction "CI_C_IN") (pintype "bidirectional"))
    )
    (net (code "12") (name "CTS") (class "Default")
      (node (ref "SERIAL") (pin "5") (pinfunction "S_5") (pintype "passive"))
    )
    (net (code "13") (name "DO_1") (class "Default")
      (node (ref "U11") (pin "D_OUT") (pinfunction "DO_D_OUT") (pintype "bidirectional"))
      (node (ref "U12") (pin "D_IN") (pinfunction "DI_D_IN") (pintype "bidirectional"))
    )
    (net (code "14") (name "DO_2") (class "Default")
      (node (ref "U19") (pin "D_OUT") (pinfunction "DO_D_OUT") (pintype "bidirectional"))
      (node (ref "U20") (pin "D_IN") (pinfunction "DI_D_IN") (pintype "bidirectional"))
    )
    (net (code "15") (name "DTR") (class "Default")
      (node (ref "C2") (pin "1") (pinfunction "1_1") (pintype "passive"))
      (node (ref "SERIAL") (pin "1") (pinfunction "S_1") (pintype "passive"))
    )
    (net (code "16") (name "FB") (class "Default")
      (node (ref "FB") (pin "TP") (pinfunction "TP_TP") (pintype "input"))
      (node (ref "RF1") (pin "2") (pinfunction "2_2") (pintype "passive"))
      (node (ref "RF2") (pin "2") (pinfunction "2_2") (pintype "passive"))
      (node (ref "U$1") (pin "4") (pinfunction "FB_4") (pintype "input"))
    )
    (net (code "17") (name "FREQ") (class "Default")
      (node (ref "C3") (pin "1") (pinfunction "1_1") (pintype "passive"))
      (node (ref "FREQ") (pin "TP") (pinfunction "TP_TP") (pintype "input"))
      (node (ref "R3") (pin "1") (pinfunction "1_1") (pintype "passive"))
      (node (ref "U$1") (pin "3") (pinfunction "FREQ_3") (pintype "input"))
    )
    (net (code "18") (name "GND") (class "Default")
      (node (ref "APA102_C2") (pin "-") (pinfunction "-_-") (pintype "passive"))
      (node (ref "C1") (pin "C") (pinfunction "-_C") (pintype "passive"))
      (node (ref "C10") (pin "1") (pinfunction "1_1") (pintype "passive"))
      (node (ref "C11") (pin "1") (pinfunction "1_1") (pintype "passive"))
      (node (ref "C4") (pin "-") (pinfunction "-_-") (pintype "passive"))
      (node (ref "C5") (pin "2") (pinfunction "2_2") (pintype "passive"))
      (node (ref "C6") (pin "2") (pinfunction "2_2") (pintype "passive"))
      (node (ref "C7") (pin "C") (pinfunction "-_C") (pintype "passive"))
      (node (ref "C8") (pin "C") (pinfunction "-_C") (pintype "passive"))
      (node (ref "C9") (pin "C") (pinfunction "-_C") (pintype "passive"))
      (node (ref "D2") (pin "A") (pinfunction "A_A") (pintype "passive"))
      (node (ref "GND") (pin "TP") (pinfunction "TP_TP") (pintype "input"))
      (node (ref "ICSP") (pin "6") (pinfunction "6_6") (pintype "passive"))
      (node (ref "ICSP_MINI") (pin "6") (pinfunction "PWRC_6") (pintype "input"))
      (node (ref "POWER") (pin "2") (pinfunction "S_2") (pintype "passive"))
      (node (ref "R14") (pin "1") (pinfunction "1_1") (pintype "passive"))
      (node (ref "R16") (pin "1") (pinfunction "1_1") (pintype "passive"))
      (node (ref "RF2") (pin "1") (pinfunction "1_1") (pintype "passive"))
      (node (ref "SERIAL") (pin "6") (pinfunction "S_6") (pintype "passive"))
      (node (ref "T2") (pin "E") (pinfunction "E_E") (pintype "passive"))
      (node (ref "U$1") (pin "1") (pinfunction "PGND_1") (pintype "power_in"))
      (node (ref "U$1") (pin "5") (pinfunction "SGND_5") (pintype "power_in"))
      (node (ref "U1") (pin "21") (pinfunction "GND2_21") (pintype "bidirectional"))
      (node (ref "U1") (pin "3") (pinfunction "GND1_3") (pintype "bidirectional"))
      (node (ref "U1") (pin "5") (pinfunction "GND3_5") (pintype "bidirectional"))
      (node (ref "U10") (pin "GND") (pinfunction "GND_GND") (pintype "bidirectional"))
      (node (ref "U11") (pin "GND") (pinfunction "GND_GND") (pintype "bidirectional"))
      (node (ref "U12") (pin "GND") (pinfunction "GND_GND") (pintype "bidirectional"))
      (node (ref "U13") (pin "GND") (pinfunction "GND_GND") (pintype "bidirectional"))
      (node (ref "U14") (pin "GND") (pinfunction "GND_GND") (pintype "bidirectional"))
      (node (ref "U15") (pin "GND") (pinfunction "GND_GND") (pintype "bidirectional"))
      (node (ref "U16") (pin "GND") (pinfunction "GND_GND") (pintype "bidirectional"))
      (node (ref "U17") (pin "GND") (pinfunction "GND_GND") (pintype "bidirectional"))
      (node (ref "U18") (pin "GND") (pinfunction "GND_GND") (pintype "bidirectional"))
      (node (ref "U19") (pin "GND") (pinfunction "GND_GND") (pintype "bidirectional"))
      (node (ref "U2") (pin "6") (pinfunction "GND_6") (pintype "bidirectional"))
      (node (ref "U20") (pin "GND") (pinfunction "GND_GND") (pintype "bidirectional"))
      (node (ref "U21") (pin "GND") (pinfunction "GND_GND") (pintype "bidirectional"))
      (node (ref "U22") (pin "GND") (pinfunction "GND_GND") (pintype "bidirectional"))
      (node (ref "U23") (pin "GND") (pinfunction "GND_GND") (pintype "bidirectional"))
      (node (ref "U3") (pin "1") (pinfunction "ADJ_1") (pintype "input"))
      (node (ref "U4") (pin "GND") (pinfunction "GND_GND") (pintype "bidirectional"))
      (node (ref "U5") (pin "GND") (pinfunction "GND_GND") (pintype "bidirectional"))
      (node (ref "U6") (pin "GND") (pinfunction "GND_GND") (pintype "bidirectional"))
      (node (ref "U7") (pin "GND") (pinfunction "GND_GND") (pintype "bidirectional"))
      (node (ref "U8") (pin "GND") (pinfunction "GND_GND") (pintype "bidirectional"))
      (node (ref "U9") (pin "GND") (pinfunction "GND_GND") (pintype "bidirectional"))
      (node (ref "Y1") (pin "2") (pinfunction "2_2") (pintype "passive"))
    )
    (net (code "19") (name "INT") (class "Default")
      (node (ref "INT") (pin "TP") (pinfunction "TP_TP") (pintype "input"))
      (node (ref "Q1") (pin "3") (pinfunction "D_3") (pintype "bidirectional"))
      (node (ref "R9") (pin "1") (pinfunction "1_1") (pintype "passive"))
      (node (ref "U1") (pin "32") (pinfunction "PD2(INT0)_32") (pintype "bidirectional"))
    )
    (net (code "20") (name "LM2623_ENABLE") (class "Default")
      (node (ref "R15") (pin "2") (pinfunction "2_2") (pintype "passive"))
      (node (ref "R16") (pin "2") (pinfunction "2_2") (pintype "passive"))
      (node (ref "T1") (pin "C") (pinfunction "C_C") (pintype "passive"))
      (node (ref "U$1") (pin "2") (pinfunction "EN_2") (pintype "input"))
    )
    (net (code "21") (name "MISO") (class "Default")
      (node (ref "ICSP") (pin "1") (pinfunction "1_1") (pintype "passive"))
      (node (ref "ICSP_MINI") (pin "1") (pinfunction "GND_1") (pintype "power_in"))
      (node (ref "MISO") (pin "TP") (pinfunction "TP_TP") (pintype "input"))
      (node (ref "U1") (pin "16") (pinfunction "PB4(MISO)_16") (pintype "bidirectional"))
    )
    (net (code "22") (name "MOSI") (class "Default")
      (node (ref "ICSP") (pin "4") (pinfunction "4_4") (pintype "passive"))
      (node (ref "ICSP_MINI") (pin "4") (pinfunction "RXA_4") (pintype "input"))
      (node (ref "MOSI") (pin "TP") (pinfunction "TP_TP") (pintype "input"))
      (node (ref "R5") (pin "1") (pinfunction "1_1") (pintype "passive"))
      (node (ref "U1") (pin "15") (pinfunction "PB3(MOSI)_15") (pintype "bidirectional"))
    )
    (net (code "23") (name "Net-(R6-Pad1)") (class "Default")
      (node (ref "R6") (pin "1") (pinfunction "1_1") (pintype "passive"))
      (node (ref "R7") (pin "2") (pinfunction "2_2") (pintype "passive"))
      (node (ref "T1") (pin "B") (pinfunction "B_B") (pintype "passive"))
    )
    (net (code "24") (name "Net-(R14-Pad2)") (class "Default")
      (node (ref "R14") (pin "2") (pinfunction "2_2") (pintype "passive"))
      (node (ref "R7") (pin "1") (pinfunction "1_1") (pintype "passive"))
      (node (ref "T2") (pin "C") (pinfunction "C_C") (pintype "passive"))
    )
    (net (code "25") (name "Net-(R15-Pad1)") (class "Default")
      (node (ref "R15") (pin "1") (pinfunction "1_1") (pintype "passive"))
      (node (ref "T2") (pin "B") (pinfunction "B_B") (pintype "passive"))
    )
    (net (code "26") (name "Net-(U1-PB6(XTAL1))") (class "Default")
      (node (ref "R4") (pin "2") (pinfunction "2_2") (pintype "passive"))
      (node (ref "U1") (pin "7") (pinfunction "PB6(XTAL1)_7") (pintype "bidirectional"))
      (node (ref "Y1") (pin "1") (pinfunction "1_1") (pintype "passive"))
    )
    (net (code "27") (name "Net-(U1-PB7(XTAL2))") (class "Default")
      (node (ref "R4") (pin "1") (pinfunction "1_1") (pintype "passive"))
      (node (ref "U1") (pin "8") (pinfunction "PB7(XTAL2)_8") (pintype "bidirectional"))
      (node (ref "Y1") (pin "3") (pinfunction "3_3") (pintype "passive"))
    )
    (net (code "28") (name "Net-(U2-LEDA)") (class "Default")
      (node (ref "C6") (pin "1") (pinfunction "1_1") (pintype "passive"))
      (node (ref "U2") (pin "5") (pinfunction "LEDA_5") (pintype "bidirectional"))
    )
    (net (code "29") (name "Net-(U4-CO)") (class "Default")
      (node (ref "U4") (pin "CL_OUT") (pinfunction "CO_CL_OUT") (pintype "bidirectional"))
      (node (ref "U5") (pin "C_IN") (pinfunction "CI_C_IN") (pintype "bidirectional"))
    )
    (net (code "30") (name "Net-(U4-DO)") (class "Default")
      (node (ref "U4") (pin "D_OUT") (pinfunction "DO_D_OUT") (pintype "bidirectional"))
      (node (ref "U5") (pin "D_IN") (pinfunction "DI_D_IN") (pintype "bidirectional"))
    )
    (net (code "31") (name "Net-(U5-CO)") (class "Default")
      (node (ref "U5") (pin "CL_OUT") (pinfunction "CO_CL_OUT") (pintype "bidirectional"))
      (node (ref "U6") (pin "C_IN") (pinfunction "CI_C_IN") (pintype "bidirectional"))
    )
    (net (code "32") (name "Net-(U5-DO)") (class "Default")
      (node (ref "U5") (pin "D_OUT") (pinfunction "DO_D_OUT") (pintype "bidirectional"))
      (node (ref "U6") (pin "D_IN") (pinfunction "DI_D_IN") (pintype "bidirectional"))
    )
    (net (code "33") (name "Net-(U6-CO)") (class "Default")
      (node (ref "U6") (pin "CL_OUT") (pinfunction "CO_CL_OUT") (pintype "bidirectional"))
      (node (ref "U7") (pin "C_IN") (pinfunction "CI_C_IN") (pintype "bidirectional"))
    )
    (net (code "34") (name "Net-(U6-DO)") (class "Default")
      (node (ref "U6") (pin "D_OUT") (pinfunction "DO_D_OUT") (pintype "bidirectional"))
      (node (ref "U7") (pin "D_IN") (pinfunction "DI_D_IN") (pintype "bidirectional"))
    )
    (net (code "35") (name "Net-(U7-CO)") (class "Default")
      (node (ref "U7") (pin "CL_OUT") (pinfunction "CO_CL_OUT") (pintype "bidirectional"))
      (node (ref "U8") (pin "C_IN") (pinfunction "CI_C_IN") (pintype "bidirectional"))
    )
    (net (code "36") (name "Net-(U7-DO)") (class "Default")
      (node (ref "U7") (pin "D_OUT") (pinfunction "DO_D_OUT") (pintype "bidirectional"))
      (node (ref "U8") (pin "D_IN") (pinfunction "DI_D_IN") (pintype "bidirectional"))
    )
    (net (code "37") (name "Net-(U8-CO)") (class "Default")
      (node (ref "U8") (pin "CL_OUT") (pinfunction "CO_CL_OUT") (pintype "bidirectional"))
      (node (ref "U9") (pin "C_IN") (pinfunction "CI_C_IN") (pintype "bidirectional"))
    )
    (net (code "38") (name "Net-(U8-DO)") (class "Default")
      (node (ref "U8") (pin "D_OUT") (pinfunction "DO_D_OUT") (pintype "bidirectional"))
      (node (ref "U9") (pin "D_IN") (pinfunction "DI_D_IN") (pintype "bidirectional"))
    )
    (net (code "39") (name "Net-(U10-CI)") (class "Default")
      (node (ref "U10") (pin "C_IN") (pinfunction "CI_C_IN") (pintype "bidirectional"))
      (node (ref "U9") (pin "CL_OUT") (pinfunction "CO_CL_OUT") (pintype "bidirectional"))
    )
    (net (code "40") (name "Net-(U10-CO)") (class "Default")
      (node (ref "U10") (pin "CL_OUT") (pinfunction "CO_CL_OUT") (pintype "bidirectional"))
      (node (ref "U11") (pin "C_IN") (pinfunction "CI_C_IN") (pintype "bidirectional"))
    )
    (net (code "41") (name "Net-(U10-DI)") (class "Default")
      (node (ref "U10") (pin "D_IN") (pinfunction "DI_D_IN") (pintype "bidirectional"))
      (node (ref "U9") (pin "D_OUT") (pinfunction "DO_D_OUT") (pintype "bidirectional"))
    )
    (net (code "42") (name "Net-(U10-DO)") (class "Default")
      (node (ref "U10") (pin "D_OUT") (pinfunction "DO_D_OUT") (pintype "bidirectional"))
      (node (ref "U11") (pin "D_IN") (pinfunction "DI_D_IN") (pintype "bidirectional"))
    )
    (net (code "43") (name "Net-(U12-CO)") (class "Default")
      (node (ref "U12") (pin "CL_OUT") (pinfunction "CO_CL_OUT") (pintype "bidirectional"))
      (node (ref "U13") (pin "C_IN") (pinfunction "CI_C_IN") (pintype "bidirectional"))
    )
    (net (code "44") (name "Net-(U12-DO)") (class "Default")
      (node (ref "U12") (pin "D_OUT") (pinfunction "DO_D_OUT") (pintype "bidirectional"))
      (node (ref "U13") (pin "D_IN") (pinfunction "DI_D_IN") (pintype "bidirectional"))
    )
    (net (code "45") (name "Net-(U13-CO)") (class "Default")
      (node (ref "U13") (pin "CL_OUT") (pinfunction "CO_CL_OUT") (pintype "bidirectional"))
      (node (ref "U14") (pin "C_IN") (pinfunction "CI_C_IN") (pintype "bidirectional"))
    )
    (net (code "46") (name "Net-(U13-DO)") (class "Default")
      (node (ref "U13") (pin "D_OUT") (pinfunction "DO_D_OUT") (pintype "bidirectional"))
      (node (ref "U14") (pin "D_IN") (pinfunction "DI_D_IN") (pintype "bidirectional"))
    )
    (net (code "47") (name "Net-(U14-CO)") (class "Default")
      (node (ref "U14") (pin "CL_OUT") (pinfunction "CO_CL_OUT") (pintype "bidirectional"))
      (node (ref "U15") (pin "C_IN") (pinfunction "CI_C_IN") (pintype "bidirectional"))
    )
    (net (code "48") (name "Net-(U14-DO)") (class "Default")
      (node (ref "U14") (pin "D_OUT") (pinfunction "DO_D_OUT") (pintype "bidirectional"))
      (node (ref "U15") (pin "D_IN") (pinfunction "DI_D_IN") (pintype "bidirectional"))
    )
    (net (code "49") (name "Net-(U15-CO)") (class "Default")
      (node (ref "U15") (pin "CL_OUT") (pinfunction "CO_CL_OUT") (pintype "bidirectional"))
      (node (ref "U16") (pin "C_IN") (pinfunction "CI_C_IN") (pintype "bidirectional"))
    )
    (net (code "50") (name "Net-(U15-DO)") (class "Default")
      (node (ref "U15") (pin "D_OUT") (pinfunction "DO_D_OUT") (pintype "bidirectional"))
      (node (ref "U16") (pin "D_IN") (pinfunction "DI_D_IN") (pintype "bidirectional"))
    )
    (net (code "51") (name "Net-(U16-CO)") (class "Default")
      (node (ref "U16") (pin "CL_OUT") (pinfunction "CO_CL_OUT") (pintype "bidirectional"))
      (node (ref "U17") (pin "C_IN") (pinfunction "CI_C_IN") (pintype "bidirectional"))
    )
    (net (code "52") (name "Net-(U16-DO)") (class "Default")
      (node (ref "U16") (pin "D_OUT") (pinfunction "DO_D_OUT") (pintype "bidirectional"))
      (node (ref "U17") (pin "D_IN") (pinfunction "DI_D_IN") (pintype "bidirectional"))
    )
    (net (code "53") (name "Net-(U17-CO)") (class "Default")
      (node (ref "U17") (pin "CL_OUT") (pinfunction "CO_CL_OUT") (pintype "bidirectional"))
      (node (ref "U18") (pin "C_IN") (pinfunction "CI_C_IN") (pintype "bidirectional"))
    )
    (net (code "54") (name "Net-(U17-DO)") (class "Default")
      (node (ref "U17") (pin "D_OUT") (pinfunction "DO_D_OUT") (pintype "bidirectional"))
      (node (ref "U18") (pin "D_IN") (pinfunction "DI_D_IN") (pintype "bidirectional"))
    )
    (net (code "55") (name "Net-(U18-CO)") (class "Default")
      (node (ref "U18") (pin "CL_OUT") (pinfunction "CO_CL_OUT") (pintype "bidirectional"))
      (node (ref "U19") (pin "C_IN") (pinfunction "CI_C_IN") (pintype "bidirectional"))
    )
    (net (code "56") (name "Net-(U18-DO)") (class "Default")
      (node (ref "U18") (pin "D_OUT") (pinfunction "DO_D_OUT") (pintype "bidirectional"))
      (node (ref "U19") (pin "D_IN") (pinfunction "DI_D_IN") (pintype "bidirectional"))
    )
    (net (code "57") (name "Net-(U20-CO)") (class "Default")
      (node (ref "U20") (pin "CL_OUT") (pinfunction "CO_CL_OUT") (pintype "bidirectional"))
      (node (ref "U21") (pin "C_IN") (pinfunction "CI_C_IN") (pintype "bidirectional"))
    )
    (net (code "58") (name "Net-(U20-DO)") (class "Default")
      (node (ref "U20") (pin "D_OUT") (pinfunction "DO_D_OUT") (pintype "bidirectional"))
      (node (ref "U21") (pin "D_IN") (pinfunction "DI_D_IN") (pintype "bidirectional"))
    )
    (net (code "59") (name "Net-(U21-CO)") (class "Default")
      (node (ref "U21") (pin "CL_OUT") (pinfunction "CO_CL_OUT") (pintype "bidirectional"))
      (node (ref "U22") (pin "C_IN") (pinfunction "CI_C_IN") (pintype "bidirectional"))
    )
    (net (code "60") (name "Net-(U21-DO)") (class "Default")
      (node (ref "U21") (pin "D_OUT") (pinfunction "DO_D_OUT") (pintype "bidirectional"))
      (node (ref "U22") (pin "D_IN") (pinfunction "DI_D_IN") (pintype "bidirectional"))
    )
    (net (code "61") (name "Net-(U22-CO)") (class "Default")
      (node (ref "U22") (pin "CL_OUT") (pinfunction "CO_CL_OUT") (pintype "bidirectional"))
      (node (ref "U23") (pin "C_IN") (pinfunction "CI_C_IN") (pintype "bidirectional"))
    )
    (net (code "62") (name "Net-(U22-DO)") (class "Default")
      (node (ref "U22") (pin "D_OUT") (pinfunction "DO_D_OUT") (pintype "bidirectional"))
      (node (ref "U23") (pin "D_IN") (pinfunction "DI_D_IN") (pintype "bidirectional"))
    )
    (net (code "63") (name "POWER_INPUT") (class "Default")
      (node (ref "C1") (pin "A") (pinfunction "+_A") (pintype "passive"))
      (node (ref "D2") (pin "C") (pinfunction "C_C") (pintype "passive"))
      (node (ref "JP1") (pin "2") (pinfunction "2_2") (pintype "passive"))
      (node (ref "L1") (pin "P$1") (pinfunction "1_P$1") (pintype "passive"))
      (node (ref "R3") (pin "2") (pinfunction "2_2") (pintype "passive"))
      (node (ref "R6") (pin "2") (pinfunction "2_2") (pintype "passive"))
      (node (ref "T1") (pin "E") (pinfunction "E_E") (pintype "passive"))
      (node (ref "V_BOOST") (pin "TP") (pinfunction "TP_TP") (pintype "input"))
    )
    (net (code "64") (name "POWER_INPUT_CONNECTOR") (class "Default")
      (node (ref "JP1") (pin "1") (pinfunction "1_1") (pintype "passive"))
      (node (ref "POWER") (pin "1") (pinfunction "S_1") (pintype "passive"))
      (node (ref "V_BAT") (pin "TP") (pinfunction "TP_TP") (pintype "input"))
    )
    (net (code "65") (name "RST") (class "Default")
      (node (ref "C2") (pin "2") (pinfunction "2_2") (pintype "passive"))
      (node (ref "ICSP") (pin "5") (pinfunction "5_5") (pintype "passive"))
      (node (ref "ICSP_MINI") (pin "5") (pinfunction "VBATT_5") (pintype "power_in"))
      (node (ref "R2") (pin "1") (pinfunction "1_1") (pintype "passive"))
      (node (ref "RST") (pin "TP") (pinfunction "TP_TP") (pintype "input"))
      (node (ref "U1") (pin "29") (pinfunction "PC6(RESET)_29") (pintype "bidirectional"))
    )
    (net (code "66") (name "RXD") (class "Default")
      (node (ref "RXD") (pin "TP") (pinfunction "TP_TP") (pintype "input"))
      (node (ref "SERIAL") (pin "2") (pinfunction "S_2") (pintype "passive"))
      (node (ref "U1") (pin "30") (pinfunction "PD0(RXD)_30") (pintype "bidirectional"))
    )
    (net (code "67") (name "SCK") (class "Default")
      (node (ref "ICSP") (pin "3") (pinfunction "3_3") (pintype "passive"))
      (node (ref "ICSP_MINI") (pin "3") (pinfunction "TXA_3") (pintype "output"))
      (node (ref "SCK") (pin "TP") (pinfunction "TP_TP") (pintype "input"))
      (node (ref "U1") (pin "17") (pinfunction "PB5(SCK)_17") (pintype "bidirectional"))
      (node (ref "U4") (pin "C_IN") (pinfunction "CI_C_IN") (pintype "bidirectional"))
    )
    (net (code "68") (name "SCL") (class "Default")
      (node (ref "Q2") (pin "3") (pinfunction "D_3") (pintype "bidirectional"))
      (node (ref "R11") (pin "1") (pinfunction "1_1") (pintype "passive"))
      (node (ref "SCL") (pin "TP") (pinfunction "TP_TP") (pintype "input"))
      (node (ref "U1") (pin "28") (pinfunction "PC5(ADC5)_28") (pintype "bidirectional"))
    )
    (net (code "69") (name "SDA") (class "Default")
      (node (ref "Q3") (pin "3") (pinfunction "D_3") (pintype "bidirectional"))
      (node (ref "R13") (pin "1") (pinfunction "1_1") (pintype "passive"))
      (node (ref "SDA") (pin "TP") (pinfunction "TP_TP") (pintype "input"))
      (node (ref "U1") (pin "27") (pinfunction "PC4(ADC4)_27") (pintype "bidirectional"))
    )
    (net (code "70") (name "SW") (class "Default")
      (node (ref "C3") (pin "2") (pinfunction "2_2") (pintype "passive"))
      (node (ref "D1") (pin "A") (pinfunction "A_A") (pintype "passive"))
      (node (ref "L1") (pin "P$2") (pinfunction "2_P$2") (pintype "passive"))
      (node (ref "SW") (pin "TP") (pinfunction "TP_TP") (pintype "input"))
      (node (ref "U$1") (pin "8") (pinfunction "SW_8") (pintype "passive"))
    )
    (net (code "71") (name "TXD") (class "Default")
      (node (ref "SERIAL") (pin "3") (pinfunction "S_3") (pintype "passive"))
      (node (ref "TXD") (pin "TP") (pinfunction "TP_TP") (pintype "input"))
      (node (ref "U1") (pin "31") (pinfunction "PD1(TXD)_31") (pintype "bidirectional"))
    )
    (net (code "72") (name "unconnected-(U1-ADC6-Pad19)") (class "Default")
      (node (ref "U1") (pin "19") (pinfunction "ADC6_19") (pintype "bidirectional"))
    )
    (net (code "73") (name "unconnected-(U1-ADC7-Pad22)") (class "Default")
      (node (ref "U1") (pin "22") (pinfunction "ADC7_22") (pintype "bidirectional"))
    )
    (net (code "74") (name "unconnected-(U1-PB0(ICP1)-Pad12)") (class "Default")
      (node (ref "U1") (pin "12") (pinfunction "PB0(ICP1)_12") (pintype "bidirectional"))
    )
    (net (code "75") (name "unconnected-(U1-PB1(OC1A)-Pad13)") (class "Default")
      (node (ref "U1") (pin "13") (pinfunction "PB1(OC1A)_13") (pintype "bidirectional"))
    )
    (net (code "76") (name "unconnected-(U1-PB2(SS{slash}OC1B)-Pad14)") (class "Default")
      (node (ref "U1") (pin "14") (pinfunction "PB2(SS/OC1B)_14") (pintype "bidirectional"))
    )
    (net (code "77") (name "unconnected-(U1-PC0(ADC0)-Pad23)") (class "Default")
      (node (ref "U1") (pin "23") (pinfunction "PC0(ADC0)_23") (pintype "bidirectional"))
    )
    (net (code "78") (name "unconnected-(U1-PC1(ADC1)-Pad24)") (class "Default")
      (node (ref "U1") (pin "24") (pinfunction "PC1(ADC1)_24") (pintype "bidirectional"))
    )
    (net (code "79") (name "unconnected-(U1-PC2(ADC2)-Pad25)") (class "Default")
      (node (ref "U1") (pin "25") (pinfunction "PC2(ADC2)_25") (pintype "bidirectional"))
    )
    (net (code "80") (name "unconnected-(U1-PC3(ADC3)-Pad26)") (class "Default")
      (node (ref "U1") (pin "26") (pinfunction "PC3(ADC3)_26") (pintype "bidirectional"))
    )
    (net (code "81") (name "unconnected-(U1-PD3(INT1)-Pad1)") (class "Default")
      (node (ref "U1") (pin "1") (pinfunction "PD3(INT1)_1") (pintype "bidirectional"))
    )
    (net (code "82") (name "unconnected-(U1-PD5(T1)-Pad9)") (class "Default")
      (node (ref "U1") (pin "9") (pinfunction "PD5(T1)_9") (pintype "bidirectional"))
    )
    (net (code "83") (name "unconnected-(U1-PD6(AIN0)-Pad10)") (class "Default")
      (node (ref "U1") (pin "10") (pinfunction "PD6(AIN0)_10") (pintype "bidirectional"))
    )
    (net (code "84") (name "unconnected-(U1-PD7(AIN1)-Pad11)") (class "Default")
      (node (ref "U1") (pin "11") (pinfunction "PD7(AIN1)_11") (pintype "bidirectional"))
    )
    (net (code "85") (name "unconnected-(U23-CO-PadCL_OUT)") (class "Default")
      (node (ref "U23") (pin "CL_OUT") (pinfunction "CO_CL_OUT") (pintype "bidirectional"))
    )
    (net (code "86") (name "unconnected-(U23-DO-PadD_OUT)") (class "Default")
      (node (ref "U23") (pin "D_OUT") (pinfunction "DO_D_OUT") (pintype "bidirectional"))
    )
  )
)
